# SPI_Thermocouple.net
KiCad netlist of a schematic drawn in EAGLE
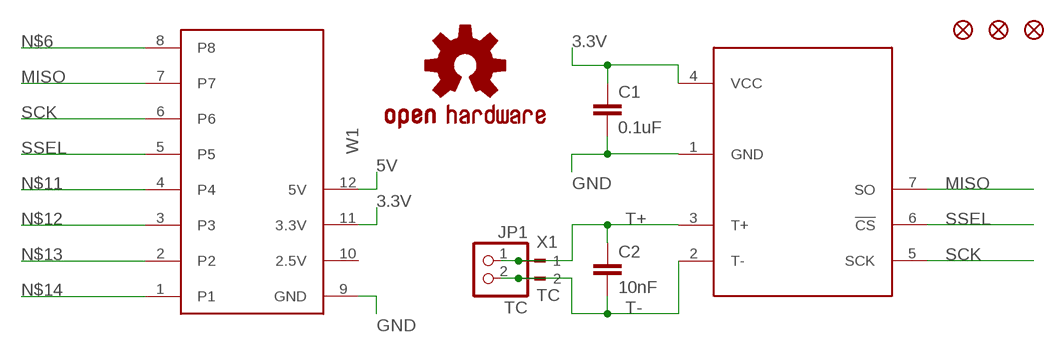
[diagram p0: schematic, sheet 1]

(export (version "E")
  (design (tool "Eeschema 10.0.6"))
  (components
    (comp (ref "C1")
      (value "0.1uF")
      (footprint "eagle-import:1206")
      (libsource (lib "eagle-import") (part "CAP1206"))
    )
    (comp (ref "C2")
      (value "10nF")
      (footprint "eagle-import:0603-CAP")
      (libsource (lib "eagle-import") (part "CAP0603-CAP"))
    )
    (comp (ref "FID1")
      (value "FIDUCIAL1X2")
      (footprint "eagle-import:FIDUCIAL-1X2")
      (libsource (lib "eagle-import") (part "FIDUCIAL1X2"))
    )
    (comp (ref "FID2")
      (value "FIDUCIAL1X2")
      (footprint "eagle-import:FIDUCIAL-1X2")
      (libsource (lib "eagle-import") (part "FIDUCIAL1X2"))
    )
    (comp (ref "FID3")
      (value "FIDUCIAL1X2")
      (footprint "eagle-import:FIDUCIAL-1X2")
      (libsource (lib "eagle-import") (part "FIDUCIAL1X2"))
    )
    (comp (ref "JP1")
      (value "TC")
      (footprint "eagle-import:1X02")
      (libsource (lib "eagle-import") (part "PINHD-1X2"))
    )
    (comp (ref "U$1")
      (value "OSHW-LOGOS")
      (footprint "eagle-import:OSHW-LOGO-S")
      (libsource (lib "eagle-import") (part "OSHW-LOGOS"))
    )
    (comp (ref "U1")
      (value "MAX31855")
      (footprint "eagle-import:SO08")
      (libsource (lib "eagle-import") (part "MAX31855"))
    )
    (comp (ref "W1")
      (value "PAPILIO-WING-8BITS")
      (footprint "eagle-import:PAPILIO-WING-8BITS")
      (libsource (lib "eagle-import") (part "PAPILIO-WING-8BITS"))
    )
    (comp (ref "X1")
      (value "TC")
      (footprint "eagle-import:180-2")
      (libsource (lib "eagle-import") (part "180-2"))
    )
  )
  (nets
    (net (code "1") (name "/3.3V") (class "Default")
      (node (ref "C1") (pin "1") (pinfunction "1_1") (pintype "passive"))
      (node (ref "U1") (pin "4") (pinfunction "VCC_4") (pintype "bidirectional"))
      (node (ref "W1") (pin "11") (pinfunction "3.3V_11") (pintype "bidirectional"))
    )
    (net (code "2") (name "/5V") (class "Default")
      (node (ref "W1") (pin "12") (pinfunction "5V_12") (pintype "bidirectional"))
    )
    (net (code "3") (name "/GND") (class "Default")
      (node (ref "C1") (pin "2") (pinfunction "2_2") (pintype "passive"))
      (node (ref "U1") (pin "1") (pinfunction "GND_1") (pintype "bidirectional"))
      (node (ref "W1") (pin "9") (pinfunction "GND_9") (pintype "bidirectional"))
    )
    (net (code "4") (name "/MISO") (class "Default")
      (node (ref "U1") (pin "7") (pinfunction "SO_7") (pintype "bidirectional"))
      (node (ref "W1") (pin "7") (pinfunction "P7_7") (pintype "bidirectional"))
    )
    (net (code "5") (name "/N$6") (class "Default")
      (node (ref "W1") (pin "8") (pinfunction "P8_8") (pintype "bidirectional"))
    )
    (net (code "6") (name "/N$11") (class "Default")
      (node (ref "W1") (pin "4") (pinfunction "P4_4") (pintype "bidirectional"))
    )
    (net (code "7") (name "/N$12") (class "Default")
      (node (ref "W1") (pin "3") (pinfunction "P3_3") (pintype "bidirectional"))
    )
    (net (code "8") (name "/N$13") (class "Default")
      (node (ref "W1") (pin "2") (pinfunction "P2_2") (pintype "bidirectional"))
    )
    (net (code "9") (name "/N$14") (class "Default")
      (node (ref "W1") (pin "1") (pinfunction "P1_1") (pintype "bidirectional"))
    )
    (net (code "10") (name "/SCK") (class "Default")
      (node (ref "U1") (pin "5") (pinfunction "SCK_5") (pintype "bidirectional"))
      (node (ref "W1") (pin "6") (pinfunction "P6_6") (pintype "bidirectional"))
    )
    (net (code "11") (name "/SSEL") (class "Default")
      (node (ref "U1") (pin "6") (pinfunction "~{CS}_6") (pintype "bidirectional"))
      (node (ref "W1") (pin "5") (pinfunction "P5_5") (pintype "bidirectional"))
    )
    (net (code "12") (name "/T+") (class "Default")
      (node (ref "C2") (pin "1") (pinfunction "1_1") (pintype "passive"))
      (node (ref "JP1") (pin "1") (pinfunction "1_1") (pintype "passive"))
      (node (ref "U1") (pin "3") (pinfunction "T+_3") (pintype "bidirectional"))
      (node (ref "X1") (pin "1") (pinfunction "1_1") (pintype "passive"))
    )
    (net (code "13") (name "/T-") (class "Default")
      (node (ref "C2") (pin "2") (pinfunction "2_2") (pintype "passive"))
      (node (ref "JP1") (pin "2") (pinfunction "2_2") (pintype "passive"))
      (node (ref "U1") (pin "2") (pinfunction "T-_2") (pintype "bidirectional"))
      (node (ref "X1") (pin "2") (pinfunction "2_2") (pintype "passive"))
    )
    (net (code "14") (name "unconnected-(W1-2.5V-Pad10)") (class "Default")
      (node (ref "W1") (pin "10") (pinfunction "2.5V_10") (pintype "bidirectional"))
    )
  )
)
